# ver1.net
KiCad netlist of a schematic drawn in EAGLE
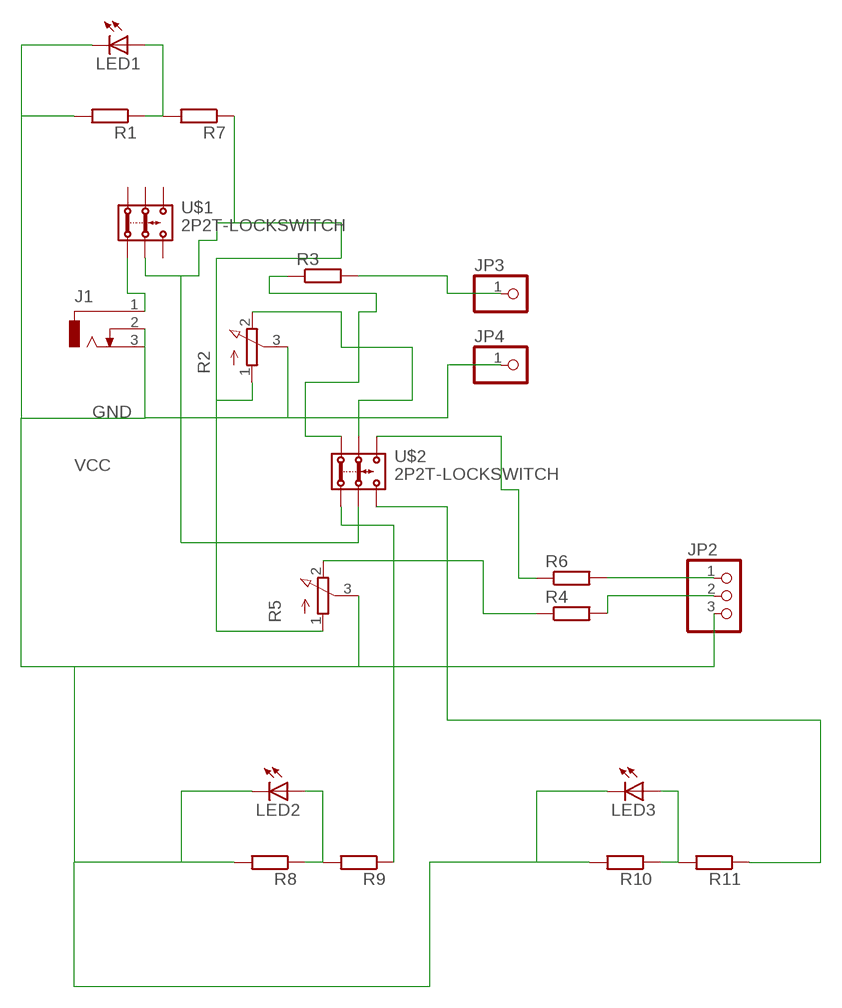
[diagram p0: schematic, sheet 1]

(export (version "E")
  (design (tool "Eeschema 10.0.6"))
  (components
    (comp (ref "J1")
      (value "DCJ0303")
      (footprint "eagle-import:DCJ0303")
      (libsource (lib "eagle-import") (part "DCJ0303"))
    )
    (comp (ref "JP2")
      (value "PINHD-1X3")
      (footprint "eagle-import:1X03")
      (libsource (lib "eagle-import") (part "PINHD-1X3"))
    )
    (comp (ref "JP3")
      (value "PINHD-1X11X01_CHANDIMA")
      (footprint "eagle-import:1X01_CHANDIMA")
      (libsource (lib "eagle-import") (part "PINHD-1X11X01_CHANDIMA"))
    )
    (comp (ref "JP4")
      (value "PINHD-1X11X01_CHANDIMA")
      (footprint "eagle-import:1X01_CHANDIMA")
      (libsource (lib "eagle-import") (part "PINHD-1X11X01_CHANDIMA"))
    )
    (comp (ref "LED1")
      (value "LEDLED5MM-CHANDIMA")
      (footprint "eagle-import:LED5MM-CHANDIMA")
      (libsource (lib "eagle-import") (part "LEDLED5MM-CHANDIMA"))
    )
    (comp (ref "LED2")
      (value "LEDLED5MM-CHANDIMA")
      (footprint "eagle-import:LED5MM-CHANDIMA")
      (libsource (lib "eagle-import") (part "LEDLED5MM-CHANDIMA"))
    )
    (comp (ref "LED3")
      (value "LEDLED5MM-CHANDIMA")
      (footprint "eagle-import:LED5MM-CHANDIMA")
      (libsource (lib "eagle-import") (part "LEDLED5MM-CHANDIMA"))
    )
    (comp (ref "R1")
      (value "R-EU_0207/10_CHANDIMA")
      (footprint "eagle-import:0207_10_CHANDIMA")
      (libsource (lib "eagle-import") (part "R-EU_0207/10_CHANDIMA"))
    )
    (comp (ref "R2")
      (value "3RP/1610N3RP_CHANDIMA")
      (footprint "eagle-import:3RP_1610N_CHANDIMA")
      (libsource (lib "eagle-import") (part "3RP/1610N3RP_CHANDIMA"))
    )
    (comp (ref "R3")
      (value "R-EU_0207/10_CHANDIMA")
      (footprint "eagle-import:0207_10_CHANDIMA")
      (libsource (lib "eagle-import") (part "R-EU_0207/10_CHANDIMA"))
    )
    (comp (ref "R4")
      (value "R-EU_0207/10_CHANDIMA")
      (footprint "eagle-import:0207_10_CHANDIMA")
      (libsource (lib "eagle-import") (part "R-EU_0207/10_CHANDIMA"))
    )
    (comp (ref "R5")
      (value "3RP/1610N3RP_CHANDIMA")
      (footprint "eagle-import:3RP_1610N_CHANDIMA")
      (libsource (lib "eagle-import") (part "3RP/1610N3RP_CHANDIMA"))
    )
    (comp (ref "R6")
      (value "R-EU_0207/10_CHANDIMA")
      (footprint "eagle-import:0207_10_CHANDIMA")
      (libsource (lib "eagle-import") (part "R-EU_0207/10_CHANDIMA"))
    )
    (comp (ref "R7")
      (value "R-EU_0207/10_CHANDIMA")
      (footprint "eagle-import:0207_10_CHANDIMA")
      (libsource (lib "eagle-import") (part "R-EU_0207/10_CHANDIMA"))
    )
    (comp (ref "R8")
      (value "R-EU_0207/10_CHANDIMA")
      (footprint "eagle-import:0207_10_CHANDIMA")
      (libsource (lib "eagle-import") (part "R-EU_0207/10_CHANDIMA"))
    )
    (comp (ref "R9")
      (value "R-EU_0207/10_CHANDIMA")
      (footprint "eagle-import:0207_10_CHANDIMA")
      (libsource (lib "eagle-import") (part "R-EU_0207/10_CHANDIMA"))
    )
    (comp (ref "R10")
      (value "R-EU_0207/10_CHANDIMA")
      (footprint "eagle-import:0207_10_CHANDIMA")
      (libsource (lib "eagle-import") (part "R-EU_0207/10_CHANDIMA"))
    )
    (comp (ref "R11")
      (value "R-EU_0207/10_CHANDIMA")
      (footprint "eagle-import:0207_10_CHANDIMA")
      (libsource (lib "eagle-import") (part "R-EU_0207/10_CHANDIMA"))
    )
    (comp (ref "U$1")
      (value "2P2T-LOCKSWITCH")
      (footprint "eagle-import:2P2T-LOCKSWITCH")
      (libsource (lib "eagle-import") (part "2P2T-LOCKSWITCH"))
    )
    (comp (ref "U$2")
      (value "2P2T-LOCKSWITCH")
      (footprint "eagle-import:2P2T-LOCKSWITCH")
      (libsource (lib "eagle-import") (part "2P2T-LOCKSWITCH"))
    )
  )
  (nets
    (net (code "1") (name "/GND") (class "Default")
      (node (ref "J1") (pin "2") (pinfunction "2_2") (pintype "passive"))
      (node (ref "J1") (pin "3") (pinfunction "3_3") (pintype "passive"))
      (node (ref "JP2") (pin "3") (pinfunction "3_3") (pintype "passive"))
      (node (ref "JP4") (pin "1") (pinfunction "1_1") (pintype "passive"))
      (node (ref "LED1") (pin "K") (pinfunction "C_K") (pintype "passive"))
      (node (ref "LED2") (pin "K") (pinfunction "C_K") (pintype "passive"))
      (node (ref "LED3") (pin "K") (pinfunction "C_K") (pintype "passive"))
      (node (ref "R1") (pin "2") (pinfunction "2_2") (pintype "passive"))
      (node (ref "R10") (pin "2") (pinfunction "2_2") (pintype "passive"))
      (node (ref "R2") (pin "3") (pinfunction "S_3") (pintype "passive"))
      (node (ref "R5") (pin "3") (pinfunction "S_3") (pintype "passive"))
      (node (ref "R8") (pin "2") (pinfunction "2_2") (pintype "passive"))
    )
    (net (code "2") (name "/VCC") (class "Default")
      (node (ref "R2") (pin "1") (pinfunction "A_1") (pintype "passive"))
      (node (ref "R5") (pin "1") (pinfunction "A_1") (pintype "passive"))
      (node (ref "R7") (pin "1") (pinfunction "1_1") (pintype "passive"))
      (node (ref "U$1") (pin "2.2") (pinfunction "2.2_2.2") (pintype "passive"))
      (node (ref "U$2") (pin "2.2") (pinfunction "2.2_2.2") (pintype "passive"))
    )
    (net (code "3") (name "Net-(J1-Pad1)") (class "Default")
      (node (ref "J1") (pin "1") (pinfunction "1_1") (pintype "passive"))
      (node (ref "U$1") (pin "1.2") (pinfunction "1.2_1.2") (pintype "passive"))
    )
    (net (code "4") (name "Net-(JP2-Pad1)") (class "Default")
      (node (ref "JP2") (pin "1") (pinfunction "1_1") (pintype "passive"))
      (node (ref "R6") (pin "2") (pinfunction "2_2") (pintype "passive"))
    )
    (net (code "5") (name "Net-(JP2-Pad2)") (class "Default")
      (node (ref "JP2") (pin "2") (pinfunction "2_2") (pintype "passive"))
      (node (ref "R4") (pin "2") (pinfunction "2_2") (pintype "passive"))
    )
    (net (code "6") (name "Net-(JP3-Pad1)") (class "Default")
      (node (ref "JP3") (pin "1") (pinfunction "1_1") (pintype "passive"))
      (node (ref "R3") (pin "2") (pinfunction "2_2") (pintype "passive"))
    )
    (net (code "7") (name "Net-(LED1-PadA)") (class "Default")
      (node (ref "LED1") (pin "A") (pinfunction "A_A") (pintype "passive"))
      (node (ref "R1") (pin "1") (pinfunction "1_1") (pintype "passive"))
      (node (ref "R7") (pin "2") (pinfunction "2_2") (pintype "passive"))
    )
    (net (code "8") (name "Net-(LED2-PadA)") (class "Default")
      (node (ref "LED2") (pin "A") (pinfunction "A_A") (pintype "passive"))
      (node (ref "R8") (pin "1") (pinfunction "1_1") (pintype "passive"))
      (node (ref "R9") (pin "2") (pinfunction "2_2") (pintype "passive"))
    )
    (net (code "9") (name "Net-(LED3-PadA)") (class "Default")
      (node (ref "LED3") (pin "A") (pinfunction "A_A") (pintype "passive"))
      (node (ref "R10") (pin "1") (pinfunction "1_1") (pintype "passive"))
      (node (ref "R11") (pin "2") (pinfunction "2_2") (pintype "passive"))
    )
    (net (code "10") (name "Net-(R2-E)") (class "Default")
      (node (ref "R2") (pin "2") (pinfunction "E_2") (pintype "passive"))
      (node (ref "U$2") (pin "2.1") (pinfunction "2.1_2.1") (pintype "passive"))
    )
    (net (code "11") (name "Net-(R3-Pad1)") (class "Default")
      (node (ref "R3") (pin "1") (pinfunction "1_1") (pintype "passive"))
      (node (ref "U$2") (pin "1.1") (pinfunction "1.1_1.1") (pintype "passive"))
    )
    (net (code "12") (name "Net-(R5-E)") (class "Default")
      (node (ref "R4") (pin "1") (pinfunction "1_1") (pintype "passive"))
      (node (ref "R5") (pin "2") (pinfunction "E_2") (pintype "passive"))
    )
    (net (code "13") (name "Net-(R6-Pad1)") (class "Default")
      (node (ref "R6") (pin "1") (pinfunction "1_1") (pintype "passive"))
      (node (ref "U$2") (pin "3.1") (pinfunction "3.1_3.1") (pintype "passive"))
    )
    (net (code "14") (name "Net-(R9-Pad1)") (class "Default")
      (node (ref "R9") (pin "1") (pinfunction "1_1") (pintype "passive"))
      (node (ref "U$2") (pin "1.2") (pinfunction "1.2_1.2") (pintype "passive"))
    )
    (net (code "15") (name "Net-(R11-Pad1)") (class "Default")
      (node (ref "R11") (pin "1") (pinfunction "1_1") (pintype "passive"))
      (node (ref "U$2") (pin "3.2") (pinfunction "3.2_3.2") (pintype "passive"))
    )
    (net (code "16") (name "unconnected-(U$1-Pad1.1)") (class "Default")
      (node (ref "U$1") (pin "1.1") (pinfunction "1.1_1.1") (pintype "passive"))
    )
    (net (code "17") (name "unconnected-(U$1-Pad2.1)") (class "Default")
      (node (ref "U$1") (pin "2.1") (pinfunction "2.1_2.1") (pintype "passive"))
    )
    (net (code "18") (name "unconnected-(U$1-Pad3.1)") (class "Default")
      (node (ref "U$1") (pin "3.1") (pinfunction "3.1_3.1") (pintype "passive"))
    )
    (net (code "19") (name "unconnected-(U$1-Pad3.2)") (class "Default")
      (node (ref "U$1") (pin "3.2") (pinfunction "3.2_3.2") (pintype "passive"))
    )
  )
)
